# power-converter.net
KiCad netlist of a schematic drawn in Altium Designer
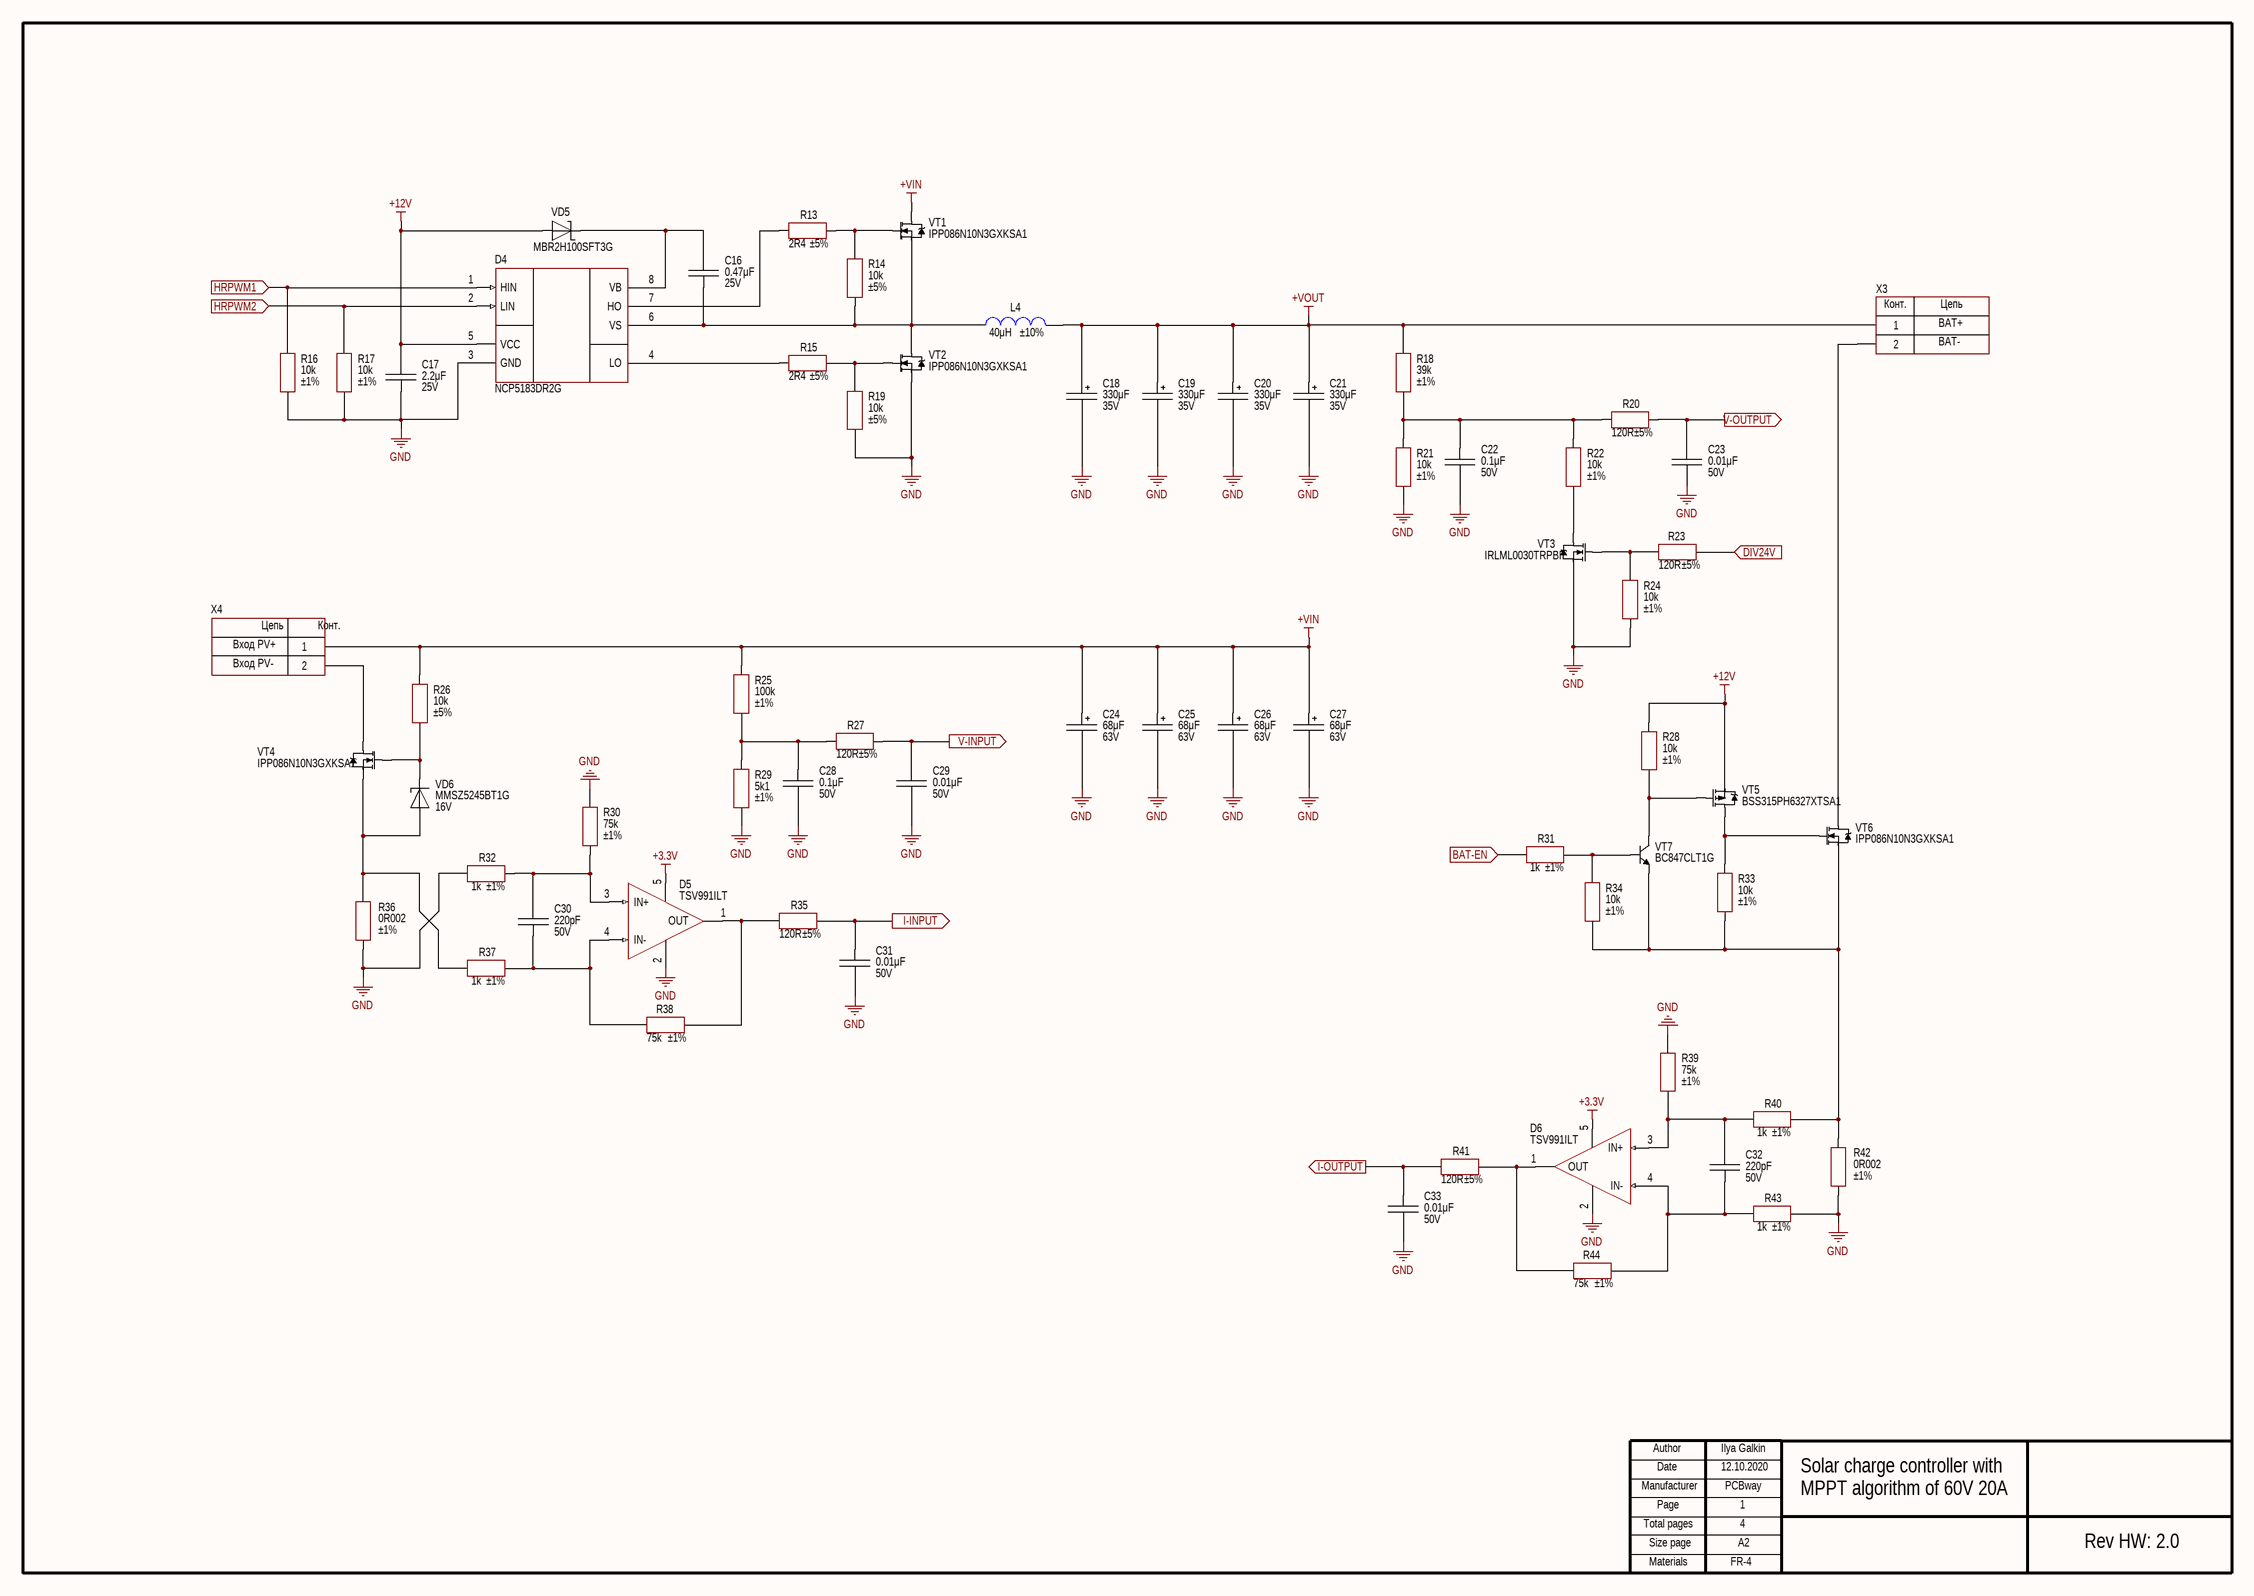
[diagram p0: power-converter.SchDoc]

(export (version "E")
  (design (tool "Eeschema 10.0.6"))
  (components
    (comp (ref "C16")
      (value "0.47μF")
      (footprint "CAP: 0805")
      (fields
        (field (name "MANUFACTURER") "Samsung")
        (field (name "PARTNUMBER") "CL21B474KAFNNNG")
        (field (name "VALUEMANUFACTURERPARTNUMBER") "Ceramic capacitor, 0.47μF, X7R, ±10%, 25V, 0805, -55...+125°C")
        (field (name "VOLTAGE") "25V")
      )
      (libsource (lib "Capacitor") (part "Ceramic_0805"))
    )
    (comp (ref "C17")
      (value "2.2μF")
      (footprint "CAP: 0805")
      (fields
        (field (name "MANUFACTURER") "Samsung")
        (field (name "PARTNUMBER") "CL21B225KAFNFNE")
        (field (name "VALUEMANUFACTURERPARTNUMBER") "Ceramic capacitor, 2.2μF, X7R, ±10%, 25V, 0805, -55...+125°C")
        (field (name "VOLTAGE") "25V")
      )
      (libsource (lib "Capacitor") (part "Ceramic_0805"))
    )
    (comp (ref "C18")
      (value "330μF")
      (footprint "CAP: D10C5H12.5")
      (fields
        (field (name "MANUFACTURER") "Panasonic")
        (field (name "PARTNUMBER") "35SEK330M")
        (field (name "VALUEMANUFACTURERPARTNUMBER") "Solid polymer capacitor, 330μF, 35V, ±20%, 18mOhm, 13x10x5 mm, -55...+105°C")
        (field (name "VOLTAGE") "35V")
      )
      (libsource (lib "Capacitor") (part "Aluminium"))
    )
    (comp (ref "C19")
      (value "330μF")
      (footprint "CAP: D10C5H12.5")
      (fields
        (field (name "MANUFACTURER") "Panasonic")
        (field (name "PARTNUMBER") "35SEK330M")
        (field (name "VALUEMANUFACTURERPARTNUMBER") "Solid polymer capacitor, 330μF, 35V, ±20%, 18mOhm, 13x10x5 mm, -55...+105°C")
        (field (name "VOLTAGE") "35V")
      )
      (libsource (lib "Capacitor") (part "Aluminium"))
    )
    (comp (ref "C20")
      (value "330μF")
      (footprint "CAP: D10C5H12.5")
      (fields
        (field (name "MANUFACTURER") "Panasonic")
        (field (name "PARTNUMBER") "35SEK330M")
        (field (name "VALUEMANUFACTURERPARTNUMBER") "Solid polymer capacitor, 330μF, 35V, ±20%, 18mOhm, 13x10x5 mm, -55...+105°C")
        (field (name "VOLTAGE") "35V")
      )
      (libsource (lib "Capacitor") (part "Aluminium"))
    )
    (comp (ref "C21")
      (value "330μF")
      (footprint "CAP: D10C5H12.5")
      (fields
        (field (name "MANUFACTURER") "Panasonic")
        (field (name "PARTNUMBER") "35SEK330M")
        (field (name "VALUEMANUFACTURERPARTNUMBER") "Solid polymer capacitor, 330μF, 35V, ±20%, 18mOhm, 13x10x5 mm, -55...+105°C")
        (field (name "VOLTAGE") "35V")
      )
      (libsource (lib "Capacitor") (part "Aluminium"))
    )
    (comp (ref "C22")
      (value "0.1μF")
      (footprint "CAP: 0603")
      (fields
        (field (name "MANUFACTURER") "Samsung")
        (field (name "PARTNUMBER") "CL10B104KB8WPND")
        (field (name "VALUEMANUFACTURERPARTNUMBER") "Ceramic capacitor, 0.1μF, X7R, ±10%, 50V, 0603, -55...+125°C")
        (field (name "VOLTAGE") "50V")
      )
      (libsource (lib "Capacitor") (part "Ceramic_0603"))
    )
    (comp (ref "C23")
      (value "0.01μF")
      (footprint "CAP: 0603")
      (fields
        (field (name "MANUFACTURER") "Samsung")
        (field (name "PARTNUMBER") "CL10B103KB8NNNC")
        (field (name "VALUEMANUFACTURERPARTNUMBER") "Ceramic capacitor, 0.01μF, X7R, ±10%, 50V, 0603, -55...+125°C")
        (field (name "VOLTAGE") "50V")
      )
      (libsource (lib "Capacitor") (part "Ceramic_0603"))
    )
    (comp (ref "C24")
      (value "68μF")
      (footprint "CAP: D10C5H12.5")
      (fields
        (field (name "MANUFACTURER") "Panasonic")
        (field (name "PARTNUMBER") "63SXE68M")
        (field (name "VALUEMANUFACTURERPARTNUMBER") "Solid polymer capacitor, 68μF, 63V, ±20%, 25mOhm, 13x10x5 mm, -55...+105°C")
        (field (name "VOLTAGE") "63V")
      )
      (libsource (lib "Capacitor") (part "Aluminium"))
    )
    (comp (ref "C25")
      (value "68μF")
      (footprint "CAP: D10C5H12.5")
      (fields
        (field (name "MANUFACTURER") "Panasonic")
        (field (name "PARTNUMBER") "63SXE68M")
        (field (name "VALUEMANUFACTURERPARTNUMBER") "Solid polymer capacitor, 68μF, 63V, ±20%, 25mOhm, 13x10x5 mm, -55...+105°C")
        (field (name "VOLTAGE") "63V")
      )
      (libsource (lib "Capacitor") (part "Aluminium"))
    )
    (comp (ref "C26")
      (value "68μF")
      (footprint "CAP: D10C5H12.5")
      (fields
        (field (name "MANUFACTURER") "Panasonic")
        (field (name "PARTNUMBER") "63SXE68M")
        (field (name "VALUEMANUFACTURERPARTNUMBER") "Solid polymer capacitor, 68μF, 63V, ±20%, 25mOhm, 13x10x5 mm, -55...+105°C")
        (field (name "VOLTAGE") "63V")
      )
      (libsource (lib "Capacitor") (part "Aluminium"))
    )
    (comp (ref "C27")
      (value "68μF")
      (footprint "CAP: D10C5H12.5")
      (fields
        (field (name "MANUFACTURER") "Panasonic")
        (field (name "PARTNUMBER") "63SXE68M")
        (field (name "VALUEMANUFACTURERPARTNUMBER") "Solid polymer capacitor, 68μF, 63V, ±20%, 25mOhm, 13x10x5 mm, -55...+105°C")
        (field (name "VOLTAGE") "63V")
      )
      (libsource (lib "Capacitor") (part "Aluminium"))
    )
    (comp (ref "C28")
      (value "0.1μF")
      (footprint "CAP: 0603")
      (fields
        (field (name "MANUFACTURER") "Samsung")
        (field (name "PARTNUMBER") "CL10B104KB8WPND")
        (field (name "VALUEMANUFACTURERPARTNUMBER") "Ceramic capacitor, 0.1μF, X7R, ±10%, 50V, 0603, -55...+125°C")
        (field (name "VOLTAGE") "50V")
      )
      (libsource (lib "Capacitor") (part "Ceramic_0603"))
    )
    (comp (ref "C29")
      (value "0.01μF")
      (footprint "CAP: 0603")
      (fields
        (field (name "MANUFACTURER") "Samsung")
        (field (name "PARTNUMBER") "CL10B103KB8NNNC")
        (field (name "VALUEMANUFACTURERPARTNUMBER") "Ceramic capacitor, 0.01μF, X7R, ±10%, 50V, 0603, -55...+125°C")
        (field (name "VOLTAGE") "50V")
      )
      (libsource (lib "Capacitor") (part "Ceramic_0603"))
    )
    (comp (ref "C30")
      (value "220pF")
      (footprint "CAP: 0603")
      (fields
        (field (name "MANUFACTURER") "Samsung")
        (field (name "PARTNUMBER") "CL10B221KB8NFNC")
        (field (name "VALUEMANUFACTURERPARTNUMBER") "Ceramic capacitor, 220pF, X7R, ±10%, 50V, 0603, -55...+125°C")
        (field (name "VOLTAGE") "50V")
      )
      (libsource (lib "Capacitor") (part "Ceramic_0603"))
    )
    (comp (ref "C31")
      (value "0.01μF")
      (footprint "CAP: 0603")
      (fields
        (field (name "MANUFACTURER") "Samsung")
        (field (name "PARTNUMBER") "CL10B103KB8NNNC")
        (field (name "VALUEMANUFACTURERPARTNUMBER") "Ceramic capacitor, 0.01μF, X7R, ±10%, 50V, 0603, -55...+125°C")
        (field (name "VOLTAGE") "50V")
      )
      (libsource (lib "Capacitor") (part "Ceramic_0603"))
    )
    (comp (ref "C32")
      (value "220pF")
      (footprint "CAP: 0603")
      (fields
        (field (name "MANUFACTURER") "Samsung")
        (field (name "PARTNUMBER") "CL10B221KB8NFNC")
        (field (name "VALUEMANUFACTURERPARTNUMBER") "Ceramic capacitor, 220pF, X7R, ±10%, 50V, 0603, -55...+125°C")
        (field (name "VOLTAGE") "50V")
      )
      (libsource (lib "Capacitor") (part "Ceramic_0603"))
    )
    (comp (ref "C33")
      (value "0.01μF")
      (footprint "CAP: 0603")
      (fields
        (field (name "MANUFACTURER") "Samsung")
        (field (name "PARTNUMBER") "CL10B103KB8NNNC")
        (field (name "VALUEMANUFACTURERPARTNUMBER") "Ceramic capacitor, 0.01μF, X7R, ±10%, 50V, 0603, -55...+125°C")
        (field (name "VOLTAGE") "50V")
      )
      (libsource (lib "Capacitor") (part "Ceramic_0603"))
    )
    (comp (ref "D4")
      (value "~")
      (footprint "8-SOIC")
      (description "Gate driver")
      (fields
        (field (name "MANUFACTURER") "ON Semiconductor")
        (field (name "VALUEMANUFACTURERPARTNUMBER") "Half-bridge gate driver, 600V, 500kHz, ±4.3A, supply 9...18V, -40...+125°C, 8-SOIC")
        (field (name "PARTNUMBER") "NCP5183DR2G")
      )
      (libsource (lib "ic-gate-driver") (part "NCP5183DR2G"))
    )
    (comp (ref "D5")
      (value "~")
      (footprint "SOT23-5")
      (description "OP amplifier")
      (fields
        (field (name "MANUFACTURER") "STMicroelectronics")
        (field (name "VALUEMANUFACTURERPARTNUMBER") "IC op amplifier, Rail-to-Rail, 20 MHz, 2.7...5.5V, -40...+125°C, SOT23-5")
        (field (name "PARTNUMBER") "TSV991ILT")
      )
      (libsource (lib "ic-amplifier") (part "TSV991ILT"))
    )
    (comp (ref "D6")
      (value "~")
      (footprint "SOT23-5")
      (description "OP amplifier")
      (fields
        (field (name "MANUFACTURER") "STMicroelectronics")
        (field (name "VALUEMANUFACTURERPARTNUMBER") "IC op amplifier, Rail-to-Rail, 20 MHz, 2.7...5.5V, -40...+125°C, SOT23-5")
        (field (name "PARTNUMBER") "TSV991ILT")
      )
      (libsource (lib "ic-amplifier") (part "TSV991ILT"))
    )
    (comp (ref "L4")
      (value "40μH")
      (footprint "IND: R32.8/20.1/10.7 (L)")
      (fields
        (field (name "MANUFACTURER") "Magnetics")
        (field (name "PARTNUMBER") "0077548A7")
        (field (name "VALUEMANUFACTURERPARTNUMBER") "Fixed inductor, 40μH, ±10%, R32.8/20.1/10.7, Kool Mu, µ=125, 127 нГн/витков2")
        (field (name "TOLERANCE") "±10%")
      )
      (libsource (lib "Inductor") (part "Inductor_R32.8/20.1/10.7"))
    )
    (comp (ref "R13")
      (value "2R4")
      (footprint "RES: 0805")
      (fields
        (field (name "MANUFACTURER") "Yageo")
        (field (name "PARTNUMBER") "RC0805JR-072R4L")
        (field (name "VALUEMANUFACTURERPARTNUMBER") "Resistor film, 2R4, ±5%, 0805, 0.125W, -55...+125°C")
        (field (name "TOLERANCE") "±5%")
      )
      (libsource (lib "") (part "Resistor_0805_1"))
    )
    (comp (ref "R14")
      (value "10k")
      (footprint "RES: 0805")
      (fields
        (field (name "MANUFACTURER") "Yageo")
        (field (name "PARTNUMBER") "RC0805JR-0710KL")
        (field (name "VALUEMANUFACTURERPARTNUMBER") "Resistor film, 10k, ±5%, 0805, 0.125W, -55...+125°C")
        (field (name "TOLERANCE") "±5%")
      )
      (libsource (lib "Resistor") (part "Resistor_0805"))
    )
    (comp (ref "R15")
      (value "2R4")
      (footprint "RES: 0805")
      (fields
        (field (name "MANUFACTURER") "Yageo")
        (field (name "PARTNUMBER") "RC0805JR-072R4L")
        (field (name "VALUEMANUFACTURERPARTNUMBER") "Resistor film, 2R4, ±5%, 0805, 0.125W, -55...+125°C")
        (field (name "TOLERANCE") "±5%")
      )
      (libsource (lib "") (part "Resistor_0805_1"))
    )
    (comp (ref "R16")
      (value "10k")
      (footprint "RES: 0603")
      (fields
        (field (name "MANUFACTURER") "Yageo")
        (field (name "PARTNUMBER") "AC0603FR-0710KL")
        (field (name "VALUEMANUFACTURERPARTNUMBER") "Resistor film, 10k, ±1%, 0603, 0.1W, -55...+125°C")
        (field (name "TOLERANCE") "±1%")
      )
      (libsource (lib "") (part "Resistor_0603_1"))
    )
    (comp (ref "R17")
      (value "10k")
      (footprint "RES: 0603")
      (fields
        (field (name "MANUFACTURER") "Yageo")
        (field (name "PARTNUMBER") "AC0603FR-0710KL")
        (field (name "VALUEMANUFACTURERPARTNUMBER") "Resistor film, 10k, ±1%, 0603, 0.1W, -55...+125°C")
        (field (name "TOLERANCE") "±1%")
      )
      (libsource (lib "") (part "Resistor_0603_1"))
    )
    (comp (ref "R18")
      (value "39k")
      (footprint "RES: 0603")
      (fields
        (field (name "MANUFACTURER") "Yageo")
        (field (name "PARTNUMBER") "RC0603FR-0739KL")
        (field (name "VALUEMANUFACTURERPARTNUMBER") "Resistor film, 39k, ±1%, 0603, 0.1W, -55...+125°C")
        (field (name "TOLERANCE") "±1%")
      )
      (libsource (lib "") (part "Resistor_0603_1"))
    )
    (comp (ref "R19")
      (value "10k")
      (footprint "RES: 0805")
      (fields
        (field (name "MANUFACTURER") "Yageo")
        (field (name "PARTNUMBER") "RC0805JR-0710KL")
        (field (name "VALUEMANUFACTURERPARTNUMBER") "Resistor film, 10k, ±5%, 0805, 0.125W, -55...+125°C")
        (field (name "TOLERANCE") "±5%")
      )
      (libsource (lib "Resistor") (part "Resistor_0805"))
    )
    (comp (ref "R20")
      (value "120R")
      (footprint "RES: 0603")
      (fields
        (field (name "MANUFACTURER") "Yageo")
        (field (name "PARTNUMBER") "RC0603JR-07120RL")
        (field (name "VALUEMANUFACTURERPARTNUMBER") "Resistor film, 120R, ±5%, 0603, 0.1W, -55...+125°C")
        (field (name "TOLERANCE") "±5%")
      )
      (libsource (lib "Resistor") (part "Resistor_0603"))
    )
    (comp (ref "R21")
      (value "10k")
      (footprint "RES: 0603")
      (fields
        (field (name "MANUFACTURER") "Yageo")
        (field (name "PARTNUMBER") "AC0603FR-0710KL")
        (field (name "VALUEMANUFACTURERPARTNUMBER") "Resistor film, 10k, ±1%, 0603, 0.1W, -55...+125°C")
        (field (name "TOLERANCE") "±1%")
      )
      (libsource (lib "") (part "Resistor_0603_1"))
    )
    (comp (ref "R22")
      (value "10k")
      (footprint "RES: 0603")
      (fields
        (field (name "MANUFACTURER") "Yageo")
        (field (name "PARTNUMBER") "AC0603FR-0710KL")
        (field (name "VALUEMANUFACTURERPARTNUMBER") "Resistor film, 10k, ±1%, 0603, 0.1W, -55...+125°C")
        (field (name "TOLERANCE") "±1%")
      )
      (libsource (lib "") (part "Resistor_0603_1"))
    )
    (comp (ref "R23")
      (value "120R")
      (footprint "RES: 0603")
      (fields
        (field (name "MANUFACTURER") "Yageo")
        (field (name "PARTNUMBER") "RC0603JR-07120RL")
        (field (name "VALUEMANUFACTURERPARTNUMBER") "Resistor film, 120R, ±5%, 0603, 0.1W, -55...+125°C")
        (field (name "TOLERANCE") "±5%")
      )
      (libsource (lib "Resistor") (part "Resistor_0603"))
    )
    (comp (ref "R24")
      (value "10k")
      (footprint "RES: 0603")
      (fields
        (field (name "MANUFACTURER") "Yageo")
        (field (name "PARTNUMBER") "AC0603FR-0710KL")
        (field (name "VALUEMANUFACTURERPARTNUMBER") "Resistor film, 10k, ±1%, 0603, 0.1W, -55...+125°C")
        (field (name "TOLERANCE") "±1%")
      )
      (libsource (lib "") (part "Resistor_0603_1"))
    )
    (comp (ref "R25")
      (value "100k")
      (footprint "RES: 0805")
      (fields
        (field (name "MANUFACTURER") "Yageo")
        (field (name "PARTNUMBER") "RC0805FR-07100KL")
        (field (name "VALUEMANUFACTURERPARTNUMBER") "Resistor film, 100k, ±1%, 0805, 0.125W, -55...+125°C")
        (field (name "TOLERANCE") "±1%")
      )
      (libsource (lib "Resistor") (part "Resistor_0805"))
    )
    (comp (ref "R26")
      (value "10k")
      (footprint "RES: 0805")
      (fields
        (field (name "MANUFACTURER") "Yageo")
        (field (name "PARTNUMBER") "RC0805JR-0710KL")
        (field (name "VALUEMANUFACTURERPARTNUMBER") "Resistor film, 10k, ±5%, 0805, 0.125W, -55...+125°C")
        (field (name "TOLERANCE") "±5%")
      )
      (libsource (lib "Resistor") (part "Resistor_0805"))
    )
    (comp (ref "R27")
      (value "120R")
      (footprint "RES: 0603")
      (fields
        (field (name "MANUFACTURER") "Yageo")
        (field (name "PARTNUMBER") "RC0603JR-07120RL")
        (field (name "VALUEMANUFACTURERPARTNUMBER") "Resistor film, 120R, ±5%, 0603, 0.1W, -55...+125°C")
        (field (name "TOLERANCE") "±5%")
      )
      (libsource (lib "Resistor") (part "Resistor_0603"))
    )
    (comp (ref "R28")
      (value "10k")
      (footprint "RES: 0603")
      (fields
        (field (name "MANUFACTURER") "Yageo")
        (field (name "PARTNUMBER") "AC0603FR-0710KL")
        (field (name "VALUEMANUFACTURERPARTNUMBER") "Resistor film, 10k, ±1%, 0603, 0.1W, -55...+125°C")
        (field (name "TOLERANCE") "±1%")
      )
      (libsource (lib "") (part "Resistor_0603_1"))
    )
    (comp (ref "R29")
      (value "5k1")
      (footprint "RES: 0603")
      (fields
        (field (name "MANUFACTURER") "Yageo")
        (field (name "PARTNUMBER") "RC0603FR-075K1L")
        (field (name "VALUEMANUFACTURERPARTNUMBER") "Resistor film, 5k1, ±1%, 0603, 0.1W, -55...+125°C")
        (field (name "TOLERANCE") "±1%")
      )
      (libsource (lib "") (part "Resistor_0603_1"))
    )
    (comp (ref "R30")
      (value "75k")
      (footprint "RES: 0603")
      (fields
        (field (name "MANUFACTURER") "Yageo")
        (field (name "PARTNUMBER") "AC0603FR-0775KL")
        (field (name "VALUEMANUFACTURERPARTNUMBER") "Resistor film, 75k, ±1%, 0603, 0.1W, -55...+125°C")
        (field (name "TOLERANCE") "±1%")
      )
      (libsource (lib "") (part "Resistor_0603_1"))
    )
    (comp (ref "R31")
      (value "1k")
      (footprint "RES: 0603")
      (fields
        (field (name "MANUFACTURER") "Yageo")
        (field (name "PARTNUMBER") "RC0603FR-071KL")
        (field (name "VALUEMANUFACTURERPARTNUMBER") "Resistor film, 1k, ±1%, 0603, 0.1W, -55...+125°C")
        (field (name "TOLERANCE") "±1%")
      )
      (libsource (lib "Resistor") (part "Resistor_0603"))
    )
    (comp (ref "R32")
      (value "1k")
      (footprint "RES: 0603")
      (fields
        (field (name "MANUFACTURER") "Yageo")
        (field (name "PARTNUMBER") "RC0603FR-071KL")
        (field (name "VALUEMANUFACTURERPARTNUMBER") "Resistor film, 1k, ±1%, 0603, 0.1W, -55...+125°C")
        (field (name "TOLERANCE") "±1%")
      )
      (libsource (lib "Resistor") (part "Resistor_0603"))
    )
    (comp (ref "R33")
      (value "10k")
      (footprint "RES: 0603")
      (fields
        (field (name "MANUFACTURER") "Yageo")
        (field (name "PARTNUMBER") "AC0603FR-0710KL")
        (field (name "VALUEMANUFACTURERPARTNUMBER") "Resistor film, 10k, ±1%, 0603, 0.1W, -55...+125°C")
        (field (name "TOLERANCE") "±1%")
      )
      (libsource (lib "") (part "Resistor_0603_1"))
    )
    (comp (ref "R34")
      (value "10k")
      (footprint "RES: 0603")
      (fields
        (field (name "MANUFACTURER") "Yageo")
        (field (name "PARTNUMBER") "AC0603FR-0710KL")
        (field (name "VALUEMANUFACTURERPARTNUMBER") "Resistor film, 10k, ±1%, 0603, 0.1W, -55...+125°C")
        (field (name "TOLERANCE") "±1%")
      )
      (libsource (lib "") (part "Resistor_0603_1"))
    )
    (comp (ref "R35")
      (value "120R")
      (footprint "RES: 0603")
      (fields
        (field (name "MANUFACTURER") "Yageo")
        (field (name "PARTNUMBER") "RC0603JR-07120RL")
        (field (name "VALUEMANUFACTURERPARTNUMBER") "Resistor film, 120R, ±5%, 0603, 0.1W, -55...+125°C")
        (field (name "TOLERANCE") "±5%")
      )
      (libsource (lib "Resistor") (part "Resistor_0603"))
    )
    (comp (ref "R36")
      (value "0R002")
      (footprint "RES: CSS2H (2512)")
      (fields
        (field (name "MANUFACTURER") "Yageo")
        (field (name "PARTNUMBER") "PA2512FKM7W0R002E")
        (field (name "VALUEMANUFACTURERPARTNUMBER") "Resistor film, 0R002, ±1%, 2512, 2W, -55...+170°C")
        (field (name "TOLERANCE") "±1%")
      )
      (libsource (lib "Resistor") (part "Shunt"))
    )
    (comp (ref "R37")
      (value "1k")
      (footprint "RES: 0603")
      (fields
        (field (name "MANUFACTURER") "Yageo")
        (field (name "PARTNUMBER") "RC0603FR-071KL")
        (field (name "VALUEMANUFACTURERPARTNUMBER") "Resistor film, 1k, ±1%, 0603, 0.1W, -55...+125°C")
        (field (name "TOLERANCE") "±1%")
      )
      (libsource (lib "Resistor") (part "Resistor_0603"))
    )
    (comp (ref "R38")
      (value "75k")
      (footprint "RES: 0603")
      (fields
        (field (name "MANUFACTURER") "Yageo")
        (field (name "PARTNUMBER") "AC0603FR-0775KL")
        (field (name "VALUEMANUFACTURERPARTNUMBER") "Resistor film, 75k, ±1%, 0603, 0.1W, -55...+125°C")
        (field (name "TOLERANCE") "±1%")
      )
      (libsource (lib "") (part "Resistor_0603_2"))
    )
    (comp (ref "R39")
      (value "75k")
      (footprint "RES: 0603")
      (fields
        (field (name "MANUFACTURER") "Yageo")
        (field (name "PARTNUMBER") "AC0603FR-0775KL")
        (field (name "VALUEMANUFACTURERPARTNUMBER") "Resistor film, 75k, ±1%, 0603, 0.1W, -55...+125°C")
        (field (name "TOLERANCE") "±1%")
      )
      (libsource (lib "") (part "Resistor_0603_1"))
    )
    (comp (ref "R40")
      (value "1k")
      (footprint "RES: 0603")
      (fields
        (field (name "MANUFACTURER") "Yageo")
        (field (name "PARTNUMBER") "RC0603FR-071KL")
        (field (name "VALUEMANUFACTURERPARTNUMBER") "Resistor film, 1k, ±1%, 0603, 0.1W, -55...+125°C")
        (field (name "TOLERANCE") "±1%")
      )
      (libsource (lib "Resistor") (part "Resistor_0603"))
    )
    (comp (ref "R41")
      (value "120R")
      (footprint "RES: 0603")
      (fields
        (field (name "MANUFACTURER") "Yageo")
        (field (name "PARTNUMBER") "RC0603JR-07120RL")
        (field (name "VALUEMANUFACTURERPARTNUMBER") "Resistor film, 120R, ±5%, 0603, 0.1W, -55...+125°C")
        (field (name "TOLERANCE") "±5%")
      )
      (libsource (lib "Resistor") (part "Resistor_0603"))
    )
    (comp (ref "R42")
      (value "0R002")
      (footprint "RES: CSS2H (2512)")
      (fields
        (field (name "MANUFACTURER") "Yageo")
        (field (name "PARTNUMBER") "PA2512FKM7W0R002E")
        (field (name "VALUEMANUFACTURERPARTNUMBER") "Resistor film, 0R002, ±1%, 2512, 2W, -55...+170°C")
        (field (name "TOLERANCE") "±1%")
      )
      (libsource (lib "Resistor") (part "Shunt"))
    )
    (comp (ref "R43")
      (value "1k")
      (footprint "RES: 0603")
      (fields
        (field (name "MANUFACTURER") "Yageo")
        (field (name "PARTNUMBER") "RC0603FR-071KL")
        (field (name "VALUEMANUFACTURERPARTNUMBER") "Resistor film, 1k, ±1%, 0603, 0.1W, -55...+125°C")
        (field (name "TOLERANCE") "±1%")
      )
      (libsource (lib "Resistor") (part "Resistor_0603"))
    )
    (comp (ref "R44")
      (value "75k")
      (footprint "RES: 0603")
      (fields
        (field (name "MANUFACTURER") "Yageo")
        (field (name "PARTNUMBER") "AC0603FR-0775KL")
        (field (name "VALUEMANUFACTURERPARTNUMBER") "Resistor film, 75k, ±1%, 0603, 0.1W, -55...+125°C")
        (field (name "TOLERANCE") "±1%")
      )
      (libsource (lib "") (part "Resistor_0603_2"))
    )
    (comp (ref "VD5")
      (value "~")
      (footprint "DIODE: SOD123F")
      (fields
        (field (name "MANUFACTURER") "ON Semiconductor")
        (field (name "VALUEMANUFACTURERPARTNUMBER") "Schottky diode, 100V, 2A, 840mV, 15pF, SOD-123F, -55...+150°C")
        (field (name "VOLTAGE") "100V")
        (field (name "PARTNUMBER") "MBR2H100SFT3G")
      )
      (libsource (lib "Diode") (part "Schottky_single"))
    )
    (comp (ref "VD6")
      (value "~")
      (footprint "DIODE: SOD123")
      (fields
        (field (name "MANUFACTURER") "ON Semiconductor")
        (field (name "VALUEMANUFACTURERPARTNUMBER") "Zener diode, 16V, 500mW, 0.9V, 16Ohm, SOD-123, -55...+150°C")
        (field (name "VOLTAGE") "16V")
        (field (name "PARTNUMBER") "MMSZ5245BT1G")
      )
      (libsource (lib "Diode") (part "Zener_single"))
    )
    (comp (ref "VT1")
      (value "~")
      (footprint "TO220(H)")
      (fields
        (field (name "MANUFACTURER") "Infineon Technologies")
        (field (name "VALUEMANUFACTURERPARTNUMBER") "MOSFET N-channel transistor, 100V, 80A, 55nC, 125W, 8.6mOhm, 3980pF, TO-220, -55...+150°C")
        (field (name "PARTNUMBER") "IPP086N10N3GXKSA1")
      )
      (libsource (lib "transistor") (part "MOSFET_N_123"))
    )
    (comp (ref "VT2")
      (value "~")
      (footprint "TO220(H)")
      (fields
        (field (name "MANUFACTURER") "Infineon Technologies")
        (field (name "VALUEMANUFACTURERPARTNUMBER") "MOSFET N-channel transistor, 100V, 80A, 55nC, 125W, 8.6mOhm, 3980pF, TO-220, -55...+150°C")
        (field (name "PARTNUMBER") "IPP086N10N3GXKSA1")
      )
      (libsource (lib "transistor") (part "MOSFET_N_123"))
    )
    (comp (ref "VT3")
      (value "~")
      (footprint "SOT23")
      (fields
        (field (name "MANUFACTURER") "Infineon Technologies")
        (field (name "VALUEMANUFACTURERPARTNUMBER") "MOSFET N-channel transistor, 30V, 5.3A, 2.6nC, 1.3W, 27mOhm, 382pF, SOT-23, -55...+150°C")
        (field (name "PARTNUMBER") "IRLML0030TRPBF")
      )
      (libsource (lib "Transistor") (part "MOSFET_N_132"))
    )
    (comp (ref "VT4")
      (value "~")
      (footprint "TO220(H)")
      (fields
        (field (name "MANUFACTURER") "Infineon Technologies")
        (field (name "VALUEMANUFACTURERPARTNUMBER") "MOSFET N-channel transistor, 100V, 80A, 55nC, 125W, 8.6mOhm, 3980pF, TO-220, -55...+150°C")
        (field (name "PARTNUMBER") "IPP086N10N3GXKSA1")
      )
      (libsource (lib "transistor") (part "MOSFET_N_123"))
    )
    (comp (ref "VT5")
      (value "~")
      (footprint "SOT23")
      (fields
        (field (name "MANUFACTURER") "Infineon Technologies")
        (field (name "VALUEMANUFACTURERPARTNUMBER") "MOSFET P-channel transistor, 30V, 1.5A, 2.3nC, 500mW, 150mOhm, 282pF, SOT-23, -55...+150°C")
        (field (name "PARTNUMBER") "BSS315PH6327XTSA1")
      )
      (libsource (lib "transistor") (part "MOSFET_P_132"))
    )
    (comp (ref "VT6")
      (value "~")
      (footprint "TO220(H)")
      (fields
        (field (name "MANUFACTURER") "Infineon Technologies")
        (field (name "VALUEMANUFACTURERPARTNUMBER") "MOSFET N-channel transistor, 100V, 80A, 55nC, 125W, 8.6mOhm, 3980pF, TO-220, -55...+150°C")
        (field (name "PARTNUMBER") "IPP086N10N3GXKSA1")
      )
      (libsource (lib "transistor") (part "MOSFET_N_123"))
    )
    (comp (ref "VT7")
      (value "~")
      (footprint "SOT23")
      (fields
        (field (name "MANUFACTURER") "ON Semiconductor")
        (field (name "VALUEMANUFACTURERPARTNUMBER") "NPN transistor, 45V, 100mA, 100MHz, 300mW, 0.6V, 420, SOT-23, -55...+125°C")
        (field (name "PARTNUMBER") "BC847CLT1G")
      )
      (libsource (lib "transistor") (part "BJT_NPN_132"))
    )
    (comp (ref "X3")
      (value "~")
      (footprint "CON: XT60PW-M")
      (fields
        (field (name "MANUFACTURER") "AMASS")
        (field (name "VALUEMANUFACTURERPARTNUMBER") "Power connector, 2pin, 7.2mm, 500V, 60A")
        (field (name "PARTNUMBER") "XT60PW-M")
      )
      (libsource (lib "") (part "Connector_XT_2pin_1"))
    )
    (comp (ref "X4")
      (value "~")
      (footprint "CON: XT60PW-M")
      (fields
        (field (name "MANUFACTURER") "AMASS")
        (field (name "VALUEMANUFACTURERPARTNUMBER") "Power connector, 2pin, 7.2mm, 500V, 60A")
        (field (name "PARTNUMBER") "XT60PW-M")
      )
      (libsource (lib "Connector") (part "Connector_XT_2pin"))
    )
  )
  (nets
    (net (code "1") (name "+3.3V") (class "Default")
      (node (ref "D5") (pin "5") (pinfunction "V+_5") (pintype "power_in"))
      (node (ref "D6") (pin "5") (pinfunction "V+_5") (pintype "power_in"))
    )
    (net (code "2") (name "+12V") (class "Default")
      (node (ref "C17") (pin "2") (pinfunction "2_2") (pintype "power_in"))
      (node (ref "D4") (pin "5") (pinfunction "VCC_5") (pintype "passive"))
      (node (ref "R28") (pin "2") (pinfunction "2_2") (pintype "passive"))
      (node (ref "VD5") (pin "1") (pinfunction "1_1") (pintype "passive"))
      (node (ref "VT5") (pin "2") (pinfunction "S_2") (pintype "passive"))
    )
    (net (code "3") (name "+VIN") (class "Default")
      (node (ref "C24") (pin "1") (pinfunction "1_1") (pintype "power_in"))
      (node (ref "C25") (pin "1") (pinfunction "1_1") (pintype "power_in"))
      (node (ref "C26") (pin "1") (pinfunction "1_1") (pintype "power_in"))
      (node (ref "C27") (pin "1") (pinfunction "1_1") (pintype "power_in"))
      (node (ref "R25") (pin "2") (pinfunction "2_2") (pintype "passive"))
      (node (ref "R26") (pin "2") (pinfunction "2_2") (pintype "passive"))
      (node (ref "VT1") (pin "2") (pinfunction "D_2") (pintype "passive"))
      (node (ref "X4") (pin "1") (pinfunction "1_1") (pintype "passive"))
    )
    (net (code "4") (name "+VOUT") (class "Default")
      (node (ref "C18") (pin "1") (pinfunction "1_1") (pintype "power_in"))
      (node (ref "C19") (pin "1") (pinfunction "1_1") (pintype "power_in"))
      (node (ref "C20") (pin "1") (pinfunction "1_1") (pintype "power_in"))
      (node (ref "C21") (pin "1") (pinfunction "1_1") (pintype "power_in"))
      (node (ref "L4") (pin "1") (pinfunction "1_1") (pintype "passive"))
      (node (ref "R18") (pin "2") (pinfunction "2_2") (pintype "passive"))
      (node (ref "X3") (pin "1") (pinfunction "1_1") (pintype "passive"))
    )
    (net (code "5") (name "/BAT-EN") (class "Default")
      (node (ref "R31") (pin "1") (pinfunction "1_1") (pintype "passive"))
    )
    (net (code "6") (name "/DIV24V") (class "Default")
      (node (ref "R23") (pin "2") (pinfunction "2_2") (pintype "passive"))
    )
    (net (code "7") (name "/HRPWM1") (class "Default")
      (node (ref "D4") (pin "1") (pinfunction "HIN_1") (pintype "input"))
      (node (ref "R16") (pin "2") (pinfunction "2_2") (pintype "passive"))
    )
    (net (code "8") (name "/HRPWM2") (class "Default")
      (node (ref "D4") (pin "2") (pinfunction "LIN_2") (pintype "input"))
      (node (ref "R17") (pin "2") (pinfunction "2_2") (pintype "passive"))
    )
    (net (code "9") (name "/I-INPUT") (class "Default")
      (node (ref "C31") (pin "2") (pinfunction "2_2") (pintype "power_in"))
      (node (ref "R35") (pin "2") (pinfunction "2_2") (pintype "passive"))
    )
    (net (code "10") (name "/I-OUTPUT") (class "Default")
      (node (ref "C33") (pin "2") (pinfunction "2_2") (pintype "power_in"))
      (node (ref "R41") (pin "1") (pinfunction "1_1") (pintype "passive"))
    )
    (net (code "11") (name "/V-INPUT") (class "Default")
      (node (ref "C29") (pin "2") (pinfunction "2_2") (pintype "power_in"))
      (node (ref "R27") (pin "2") (pinfunction "2_2") (pintype "passive"))
    )
    (net (code "12") (name "/V-OUTPUT") (class "Default")
      (node (ref "C23") (pin "2") (pinfunction "2_2") (pintype "power_in"))
      (node (ref "R20") (pin "2") (pinfunction "2_2") (pintype "passive"))
    )
    (net (code "13") (name "GND") (class "Default")
      (node (ref "C17") (pin "1") (pinfunction "1_1") (pintype "power_in"))
      (node (ref "C18") (pin "2") (pinfunction "2_2") (pintype "power_in"))
      (node (ref "C19") (pin "2") (pinfunction "2_2") (pintype "power_in"))
      (node (ref "C20") (pin "2") (pinfunction "2_2") (pintype "power_in"))
      (node (ref "C21") (pin "2") (pinfunction "2_2") (pintype "power_in"))
      (node (ref "C22") (pin "1") (pinfunction "1_1") (pintype "power_in"))
      (node (ref "C23") (pin "1") (pinfunction "1_1") (pintype "power_in"))
      (node (ref "C24") (pin "2") (pinfunction "2_2") (pintype "power_in"))
      (node (ref "C25") (pin "2") (pinfunction "2_2") (pintype "power_in"))
      (node (ref "C26") (pin "2") (pinfunction "2_2") (pintype "power_in"))
      (node (ref "C27") (pin "2") (pinfunction "2_2") (pintype "power_in"))
      (node (ref "C28") (pin "1") (pinfunction "1_1") (pintype "power_in"))
      (node (ref "C29") (pin "1") (pinfunction "1_1") (pintype "power_in"))
      (node (ref "C31") (pin "1") (pinfunction "1_1") (pintype "power_in"))
      (node (ref "C33") (pin "1") (pinfunction "1_1") (pintype "power_in"))
      (node (ref "D4") (pin "3") (pinfunction "GND_3") (pintype "passive"))
      (node (ref "D5") (pin "2") (pinfunction "V-_2") (pintype "power_in"))
      (node (ref "D6") (pin "2") (pinfunction "V-_2") (pintype "power_in"))
      (node (ref "R16") (pin "1") (pinfunction "1_1") (pintype "passive"))
      (node (ref "R17") (pin "1") (pinfunction "1_1") (pintype "passive"))
      (node (ref "R19") (pin "1") (pinfunction "1_1") (pintype "passive"))
      (node (ref "R21") (pin "1") (pinfunction "1_1") (pintype "passive"))
      (node (ref "R24") (pin "1") (pinfunction "1_1") (pintype "passive"))
      (node (ref "R29") (pin "1") (pinfunction "1_1") (pintype "passive"))
      (node (ref "R30") (pin "2") (pinfunction "2_2") (pintype "passive"))
      (node (ref "R32") (pin "1") (pinfunction "1_1") (pintype "passive"))
      (node (ref "R36") (pin "1") (pinfunction "1_1") (pintype "passive"))
      (node (ref "R39") (pin "2") (pinfunction "2_2") (pintype "passive"))
      (node (ref "R42") (pin "1") (pinfunction "1_1") (pintype "passive"))
      (node (ref "R43") (pin "2") (pinfunction "2_2") (pintype "passive"))
      (node (ref "VT2") (pin "3") (pinfunction "S_3") (pintype "passive"))
      (node (ref "VT3") (pin "2") (pinfunction "S_2") (pintype "passive"))
    )
    (net (code "14") (name "Net-(C22-Pad2)") (class "Default")
      (node (ref "C22") (pin "2") (pinfunction "2_2") (pintype "power_in"))
      (node (ref "R18") (pin "1") (pinfunction "1_1") (pintype "passive"))
      (node (ref "R20") (pin "1") (pinfunction "1_1") (pintype "passive"))
      (node (ref "R21") (pin "2") (pinfunction "2_2") (pintype "passive"))
      (node (ref "R22") (pin "2") (pinfunction "2_2") (pintype "passive"))
    )
    (net (code "15") (name "Net-(C28-Pad2)") (class "Default")
      (node (ref "C28") (pin "2") (pinfunction "2_2") (pintype "power_in"))
      (node (ref "R25") (pin "1") (pinfunction "1_1") (pintype "passive"))
      (node (ref "R27") (pin "1") (pinfunction "1_1") (pintype "passive"))
      (node (ref "R29") (pin "2") (pinfunction "2_2") (pintype "passive"))
    )
    (net (code "16") (name "Net-(D4-HO)") (class "Default")
      (node (ref "D4") (pin "7") (pinfunction "HO_7") (pintype "passive"))
      (node (ref "R13") (pin "2") (pinfunction "2_2") (pintype "passive"))
    )
    (net (code "17") (name "Net-(D4-LO)") (class "Default")
      (node (ref "D4") (pin "4") (pinfunction "LO_4") (pintype "passive"))
      (node (ref "R15") (pin "2") (pinfunction "2_2") (pintype "passive"))
    )
    (net (code "18") (name "Net-(D4-VB)") (class "Default")
      (node (ref "C16") (pin "2") (pinfunction "2_2") (pintype "power_in"))
      (node (ref "D4") (pin "8") (pinfunction "VB_8") (pintype "passive"))
      (node (ref "VD5") (pin "2") (pinfunction "2_2") (pintype "passive"))
    )
    (net (code "19") (name "Net-(D4-VS)") (class "Default")
      (node (ref "C16") (pin "1") (pinfunction "1_1") (pintype "power_in"))
      (node (ref "D4") (pin "6") (pinfunction "VS_6") (pintype "passive"))
      (node (ref "L4") (pin "2") (pinfunction "2_2") (pintype "passive"))
      (node (ref "R14") (pin "1") (pinfunction "1_1") (pintype "passive"))
      (node (ref "VT1") (pin "3") (pinfunction "S_3") (pintype "passive"))
      (node (ref "VT2") (pin "2") (pinfunction "D_2") (pintype "passive"))
    )
    (net (code "20") (name "Net-(D5-IN+)") (class "Default")
      (node (ref "C30") (pin "2") (pinfunction "2_2") (pintype "power_in"))
      (node (ref "D5") (pin "3") (pinfunction "IN+_3") (pintype "input"))
      (node (ref "R30") (pin "1") (pinfunction "1_1") (pintype "passive"))
      (node (ref "R32") (pin "2") (pinfunction "2_2") (pintype "passive"))
    )
    (net (code "21") (name "Net-(D5-IN-)") (class "Default")
      (node (ref "C30") (pin "1") (pinfunction "1_1") (pintype "power_in"))
      (node (ref "D5") (pin "4") (pinfunction "IN-_4") (pintype "input"))
      (node (ref "R37") (pin "2") (pinfunction "2_2") (pintype "passive"))
      (node (ref "R38") (pin "2") (pinfunction "2_2") (pintype "passive"))
    )
    (net (code "22") (name "Net-(D5-OUT)") (class "Default")
      (node (ref "D5") (pin "1") (pinfunction "OUT_1") (pintype "power_in"))
      (node (ref "R35") (pin "1") (pinfunction "1_1") (pintype "passive"))
      (node (ref "R38") (pin "1") (pinfunction "1_1") (pintype "passive"))
    )
    (net (code "23") (name "Net-(D6-IN+)") (class "Default")
      (node (ref "C32") (pin "2") (pinfunction "2_2") (pintype "power_in"))
      (node (ref "D6") (pin "3") (pinfunction "IN+_3") (pintype "input"))
      (node (ref "R39") (pin "1") (pinfunction "1_1") (pintype "passive"))
      (node (ref "R40") (pin "1") (pinfunction "1_1") (pintype "passive"))
    )
    (net (code "24") (name "Net-(D6-IN-)") (class "Default")
      (node (ref "C32") (pin "1") (pinfunction "1_1") (pintype "power_in"))
      (node (ref "D6") (pin "4") (pinfunction "IN-_4") (pintype "input"))
      (node (ref "R43") (pin "1") (pinfunction "1_1") (pintype "passive"))
      (node (ref "R44") (pin "1") (pinfunction "1_1") (pintype "passive"))
    )
    (net (code "25") (name "Net-(D6-OUT)") (class "Default")
      (node (ref "D6") (pin "1") (pinfunction "OUT_1") (pintype "power_in"))
      (node (ref "R41") (pin "2") (pinfunction "2_2") (pintype "passive"))
      (node (ref "R44") (pin "2") (pinfunction "2_2") (pintype "passive"))
    )
    (net (code "26") (name "Net-(VD6-A)") (class "Default")
      (node (ref "R36") (pin "2") (pinfunction "2_2") (pintype "passive"))
      (node (ref "R37") (pin "1") (pinfunction "1_1") (pintype "passive"))
      (node (ref "VD6") (pin "1") (pinfunction "A_1") (pintype "passive"))
      (node (ref "VT4") (pin "3") (pinfunction "S_3") (pintype "passive"))
    )
    (net (code "27") (name "Net-(VD6-C)") (class "Default")
      (node (ref "R26") (pin "1") (pinfunction "1_1") (pintype "passive"))
      (node (ref "VD6") (pin "2") (pinfunction "C_2") (pintype "passive"))
      (node (ref "VT4") (pin "1") (pinfunction "G_1") (pintype "passive"))
    )
    (net (code "28") (name "Net-(VT1-G)") (class "Default")
      (node (ref "R13") (pin "1") (pinfunction "1_1") (pintype "passive"))
      (node (ref "R14") (pin "2") (pinfunction "2_2") (pintype "passive"))
      (node (ref "VT1") (pin "1") (pinfunction "G_1") (pintype "passive"))
    )
    (net (code "29") (name "Net-(VT2-G)") (class "Default")
      (node (ref "R15") (pin "1") (pinfunction "1_1") (pintype "passive"))
      (node (ref "R19") (pin "2") (pinfunction "2_2") (pintype "passive"))
      (node (ref "VT2") (pin "1") (pinfunction "G_1") (pintype "passive"))
    )
    (net (code "30") (name "Net-(VT3-D)") (class "Default")
      (node (ref "R22") (pin "1") (pinfunction "1_1") (pintype "passive"))
      (node (ref "VT3") (pin "3") (pinfunction "D_3") (pintype "passive"))
    )
    (net (code "31") (name "Net-(VT3-G)") (class "Default")
      (node (ref "R23") (pin "1") (pinfunction "1_1") (pintype "passive"))
      (node (ref "R24") (pin "2") (pinfunction "2_2") (pintype "passive"))
      (node (ref "VT3") (pin "1") (pinfunction "G_1") (pintype "passive"))
    )
    (net (code "32") (name "Net-(VT4-D)") (class "Default")
      (node (ref "VT4") (pin "2") (pinfunction "D_2") (pintype "passive"))
      (node (ref "X4") (pin "2") (pinfunction "2_2") (pintype "passive"))
    )
    (net (code "33") (name "Net-(VT5-D)") (class "Default")
      (node (ref "R33") (pin "2") (pinfunction "2_2") (pintype "passive"))
      (node (ref "VT5") (pin "3") (pinfunction "D_3") (pintype "passive"))
      (node (ref "VT6") (pin "1") (pinfunction "G_1") (pintype "passive"))
    )
    (net (code "34") (name "Net-(VT5-G)") (class "Default")
      (node (ref "R28") (pin "1") (pinfunction "1_1") (pintype "passive"))
      (node (ref "VT5") (pin "1") (pinfunction "G_1") (pintype "passive"))
      (node (ref "VT7") (pin "3") (pinfunction "C_3") (pintype "passive"))
    )
    (net (code "35") (name "Net-(VT6-D)") (class "Default")
      (node (ref "VT6") (pin "2") (pinfunction "D_2") (pintype "passive"))
      (node (ref "X3") (pin "2") (pinfunction "2_2") (pintype "passive"))
    )
    (net (code "36") (name "Net-(VT6-S)") (class "Default")
      (node (ref "R33") (pin "1") (pinfunction "1_1") (pintype "passive"))
      (node (ref "R34") (pin "1") (pinfunction "1_1") (pintype "passive"))
      (node (ref "R40") (pin "2") (pinfunction "2_2") (pintype "passive"))
      (node (ref "R42") (pin "2") (pinfunction "2_2") (pintype "passive"))
      (node (ref "VT6") (pin "3") (pinfunction "S_3") (pintype "passive"))
      (node (ref "VT7") (pin "2") (pinfunction "E_2") (pintype "passive"))
    )
    (net (code "37") (name "Net-(VT7-B)") (class "Default")
      (node (ref "R31") (pin "2") (pinfunction "2_2") (pintype "passive"))
      (node (ref "R34") (pin "2") (pinfunction "2_2") (pintype "passive"))
      (node (ref "VT7") (pin "1") (pinfunction "B_1") (pintype "passive"))
    )
  )
)
